# W002X.net
KiCad netlist of a schematic drawn in EAGLE
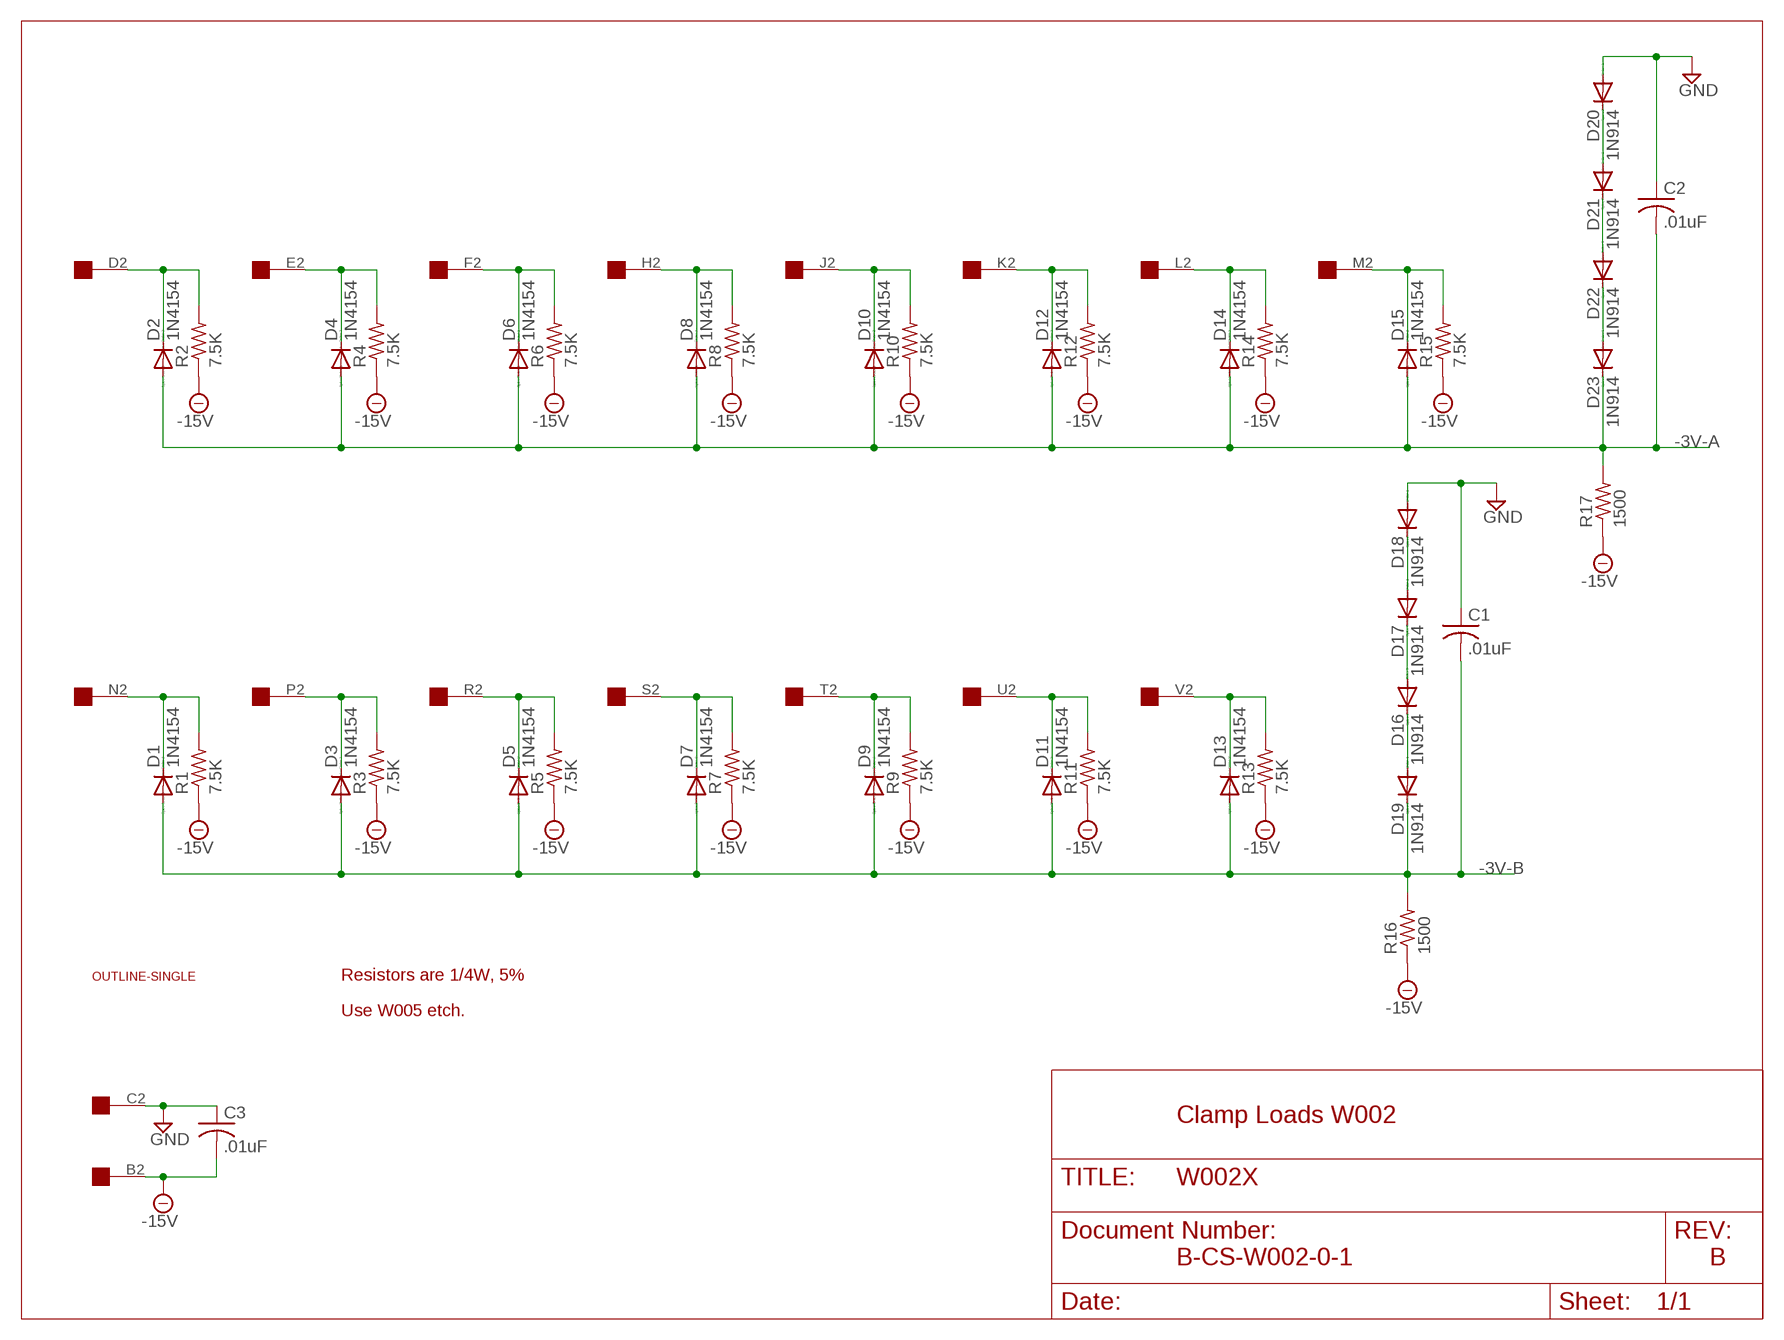
[diagram p0: schematic, sheet 1]

(export (version "E")
  (design (tool "Eeschema 10.0.6"))
  (components
    (comp (ref "C1")
      (value ".01uF")
      (footprint "eagle-import:C050-025X075")
      (libsource (lib "eagle-import") (part "C-US050-025X075"))
    )
    (comp (ref "C2")
      (value ".01uF")
      (footprint "eagle-import:C050-025X075")
      (libsource (lib "eagle-import") (part "C-US050-025X075"))
    )
    (comp (ref "C3")
      (value ".01uF")
      (footprint "eagle-import:C050-025X075")
      (libsource (lib "eagle-import") (part "C-US050-025X075"))
    )
    (comp (ref "D1")
      (value "1N4154")
      (footprint "eagle-import:DO35-10")
      (libsource (lib "eagle-import") (part "1N4148DO35-10"))
    )
    (comp (ref "D2")
      (value "1N4154")
      (footprint "eagle-import:DO35-10")
      (libsource (lib "eagle-import") (part "1N4148DO35-10"))
    )
    (comp (ref "D3")
      (value "1N4154")
      (footprint "eagle-import:DO35-10")
      (libsource (lib "eagle-import") (part "1N4148DO35-10"))
    )
    (comp (ref "D4")
      (value "1N4154")
      (footprint "eagle-import:DO35-10")
      (libsource (lib "eagle-import") (part "1N4148DO35-10"))
    )
    (comp (ref "D5")
      (value "1N4154")
      (footprint "eagle-import:DO35-10")
      (libsource (lib "eagle-import") (part "1N4148DO35-10"))
    )
    (comp (ref "D6")
      (value "1N4154")
      (footprint "eagle-import:DO35-10")
      (libsource (lib "eagle-import") (part "1N4148DO35-10"))
    )
    (comp (ref "D7")
      (value "1N4154")
      (footprint "eagle-import:DO35-10")
      (libsource (lib "eagle-import") (part "1N4148DO35-10"))
    )
    (comp (ref "D8")
      (value "1N4154")
      (footprint "eagle-import:DO35-10")
      (libsource (lib "eagle-import") (part "1N4148DO35-10"))
    )
    (comp (ref "D9")
      (value "1N4154")
      (footprint "eagle-import:DO35-10")
      (libsource (lib "eagle-import") (part "1N4148DO35-10"))
    )
    (comp (ref "D10")
      (value "1N4154")
      (footprint "eagle-import:DO35-10")
      (libsource (lib "eagle-import") (part "1N4148DO35-10"))
    )
    (comp (ref "D11")
      (value "1N4154")
      (footprint "eagle-import:DO35-10")
      (libsource (lib "eagle-import") (part "1N4148DO35-10"))
    )
    (comp (ref "D12")
      (value "1N4154")
      (footprint "eagle-import:DO35-10")
      (libsource (lib "eagle-import") (part "1N4148DO35-10"))
    )
    (comp (ref "D13")
      (value "1N4154")
      (footprint "eagle-import:DO35-10")
      (libsource (lib "eagle-import") (part "1N4148DO35-10"))
    )
    (comp (ref "D14")
      (value "1N4154")
      (footprint "eagle-import:DO35-10")
      (libsource (lib "eagle-import") (part "1N4148DO35-10"))
    )
    (comp (ref "D15")
      (value "1N4154")
      (footprint "eagle-import:DO35-10")
      (libsource (lib "eagle-import") (part "1N4148DO35-10"))
    )
    (comp (ref "D16")
      (value "1N914")
      (footprint "eagle-import:DO35-10")
      (libsource (lib "eagle-import") (part "1N4148DO35-10"))
    )
    (comp (ref "D17")
      (value "1N914")
      (footprint "eagle-import:DO35-10")
      (libsource (lib "eagle-import") (part "1N4148DO35-10"))
    )
    (comp (ref "D18")
      (value "1N914")
      (footprint "eagle-import:DO35-10")
      (libsource (lib "eagle-import") (part "1N4148DO35-10"))
    )
    (comp (ref "D19")
      (value "1N914")
      (footprint "eagle-import:DO35-10")
      (libsource (lib "eagle-import") (part "1N4148DO35-10"))
    )
    (comp (ref "D20")
      (value "1N914")
      (footprint "eagle-import:DO35-10")
      (libsource (lib "eagle-import") (part "1N4148DO35-10"))
    )
    (comp (ref "D21")
      (value "1N914")
      (footprint "eagle-import:DO35-10")
      (libsource (lib "eagle-import") (part "1N4148DO35-10"))
    )
    (comp (ref "D22")
      (value "1N914")
      (footprint "eagle-import:DO35-10")
      (libsource (lib "eagle-import") (part "1N4148DO35-10"))
    )
    (comp (ref "D23")
      (value "1N914")
      (footprint "eagle-import:DO35-10")
      (libsource (lib "eagle-import") (part "1N4148DO35-10"))
    )
    (comp (ref "R1")
      (value "7.5K")
      (footprint "eagle-import:0207_10")
      (libsource (lib "eagle-import") (part "R-US_0207/10"))
    )
    (comp (ref "R2")
      (value "7.5K")
      (footprint "eagle-import:0207_10")
      (libsource (lib "eagle-import") (part "R-US_0207/10"))
    )
    (comp (ref "R3")
      (value "7.5K")
      (footprint "eagle-import:0207_10")
      (libsource (lib "eagle-import") (part "R-US_0207/10"))
    )
    (comp (ref "R4")
      (value "7.5K")
      (footprint "eagle-import:0207_10")
      (libsource (lib "eagle-import") (part "R-US_0207/10"))
    )
    (comp (ref "R5")
      (value "7.5K")
      (footprint "eagle-import:0207_10")
      (libsource (lib "eagle-import") (part "R-US_0207/10"))
    )
    (comp (ref "R6")
      (value "7.5K")
      (footprint "eagle-import:0207_10")
      (libsource (lib "eagle-import") (part "R-US_0207/10"))
    )
    (comp (ref "R7")
      (value "7.5K")
      (footprint "eagle-import:0207_10")
      (libsource (lib "eagle-import") (part "R-US_0207/10"))
    )
    (comp (ref "R8")
      (value "7.5K")
      (footprint "eagle-import:0207_10")
      (libsource (lib "eagle-import") (part "R-US_0207/10"))
    )
    (comp (ref "R9")
      (value "7.5K")
      (footprint "eagle-import:0207_10")
      (libsource (lib "eagle-import") (part "R-US_0207/10"))
    )
    (comp (ref "R10")
      (value "7.5K")
      (footprint "eagle-import:0207_10")
      (libsource (lib "eagle-import") (part "R-US_0207/10"))
    )
    (comp (ref "R11")
      (value "7.5K")
      (footprint "eagle-import:0207_10")
      (libsource (lib "eagle-import") (part "R-US_0207/10"))
    )
    (comp (ref "R12")
      (value "7.5K")
      (footprint "eagle-import:0207_10")
      (libsource (lib "eagle-import") (part "R-US_0207/10"))
    )
    (comp (ref "R13")
      (value "7.5K")
      (footprint "eagle-import:0207_10")
      (libsource (lib "eagle-import") (part "R-US_0207/10"))
    )
    (comp (ref "R14")
      (value "7.5K")
      (footprint "eagle-import:0207_10")
      (libsource (lib "eagle-import") (part "R-US_0207/10"))
    )
    (comp (ref "R15")
      (value "7.5K")
      (footprint "eagle-import:0207_10")
      (libsource (lib "eagle-import") (part "R-US_0207/10"))
    )
    (comp (ref "R16")
      (value "1500")
      (footprint "eagle-import:0207_10")
      (libsource (lib "eagle-import") (part "R-US_0207/10"))
    )
    (comp (ref "R17")
      (value "1500")
      (footprint "eagle-import:0207_10")
      (libsource (lib "eagle-import") (part "R-US_0207/10"))
    )
    (comp (ref "U$1")
      (value "OUTLINE-SINGLE")
      (footprint "eagle-import:SINGLE")
      (libsource (lib "eagle-import") (part "OUTLINE-SINGLE"))
    )
    (comp (ref "U$2")
      (value "EDGE-1")
      (footprint "eagle-import:EDGE-CON1")
      (libsource (lib "eagle-import") (part "EDGE-1"))
    )
  )
  (nets
    (net (code "1") (name "-15V") (class "Default")
      (node (ref "C3") (pin "2") (pinfunction "2_2") (pintype "passive"))
      (node (ref "R1") (pin "1") (pinfunction "1_1") (pintype "passive"))
      (node (ref "R10") (pin "1") (pinfunction "1_1") (pintype "passive"))
      (node (ref "R11") (pin "1") (pinfunction "1_1") (pintype "passive"))
      (node (ref "R12") (pin "1") (pinfunction "1_1") (pintype "passive"))
      (node (ref "R13") (pin "1") (pinfunction "1_1") (pintype "passive"))
      (node (ref "R14") (pin "1") (pinfunction "1_1") (pintype "passive"))
      (node (ref "R15") (pin "1") (pinfunction "1_1") (pintype "passive"))
      (node (ref "R16") (pin "1") (pinfunction "1_1") (pintype "passive"))
      (node (ref "R17") (pin "1") (pinfunction "1_1") (pintype "passive"))
      (node (ref "R2") (pin "1") (pinfunction "1_1") (pintype "passive"))
      (node (ref "R3") (pin "1") (pinfunction "1_1") (pintype "passive"))
      (node (ref "R4") (pin "1") (pinfunction "1_1") (pintype "passive"))
      (node (ref "R5") (pin "1") (pinfunction "1_1") (pintype "passive"))
      (node (ref "R6") (pin "1") (pinfunction "1_1") (pintype "passive"))
      (node (ref "R7") (pin "1") (pinfunction "1_1") (pintype "passive"))
      (node (ref "R8") (pin "1") (pinfunction "1_1") (pintype "passive"))
      (node (ref "R9") (pin "1") (pinfunction "1_1") (pintype "passive"))
      (node (ref "U$2") (pin "B2") (pinfunction "1_B2") (pintype "bidirectional"))
    )
    (net (code "2") (name "/-3V-A") (class "Default")
      (node (ref "C2") (pin "2") (pinfunction "2_2") (pintype "passive"))
      (node (ref "D10") (pin "A") (pinfunction "A_A") (pintype "passive"))
      (node (ref "D12") (pin "A") (pinfunction "A_A") (pintype "passive"))
      (node (ref "D14") (pin "A") (pinfunction "A_A") (pintype "passive"))
      (node (ref "D15") (pin "A") (pinfunction "A_A") (pintype "passive"))
      (node (ref "D2") (pin "A") (pinfunction "A_A") (pintype "passive"))
      (node (ref "D23") (pin "C") (pinfunction "C_C") (pintype "passive"))
      (node (ref "D4") (pin "A") (pinfunction "A_A") (pintype "passive"))
      (node (ref "D6") (pin "A") (pinfunction "A_A") (pintype "passive"))
      (node (ref "D8") (pin "A") (pinfunction "A_A") (pintype "passive"))
      (node (ref "R17") (pin "2") (pinfunction "2_2") (pintype "passive"))
    )
    (net (code "3") (name "/-3V-B") (class "Default")
      (node (ref "C1") (pin "2") (pinfunction "2_2") (pintype "passive"))
      (node (ref "D1") (pin "A") (pinfunction "A_A") (pintype "passive"))
      (node (ref "D11") (pin "A") (pinfunction "A_A") (pintype "passive"))
      (node (ref "D13") (pin "A") (pinfunction "A_A") (pintype "passive"))
      (node (ref "D19") (pin "C") (pinfunction "C_C") (pintype "passive"))
      (node (ref "D3") (pin "A") (pinfunction "A_A") (pintype "passive"))
      (node (ref "D5") (pin "A") (pinfunction "A_A") (pintype "passive"))
      (node (ref "D7") (pin "A") (pinfunction "A_A") (pintype "passive"))
      (node (ref "D9") (pin "A") (pinfunction "A_A") (pintype "passive"))
      (node (ref "R16") (pin "2") (pinfunction "2_2") (pintype "passive"))
    )
    (net (code "4") (name "GND") (class "Default")
      (node (ref "C1") (pin "1") (pinfunction "1_1") (pintype "passive"))
      (node (ref "C2") (pin "1") (pinfunction "1_1") (pintype "passive"))
      (node (ref "C3") (pin "1") (pinfunction "1_1") (pintype "passive"))
      (node (ref "D18") (pin "A") (pinfunction "A_A") (pintype "passive"))
      (node (ref "D20") (pin "A") (pinfunction "A_A") (pintype "passive"))
      (node (ref "U$2") (pin "C2") (pinfunction "1_C2") (pintype "bidirectional"))
    )
    (net (code "5") (name "Net-(D16-PadA)") (class "Default")
      (node (ref "D16") (pin "A") (pinfunction "A_A") (pintype "passive"))
      (node (ref "D17") (pin "C") (pinfunction "C_C") (pintype "passive"))
    )
    (net (code "6") (name "Net-(D16-PadC)") (class "Default")
      (node (ref "D16") (pin "C") (pinfunction "C_C") (pintype "passive"))
      (node (ref "D19") (pin "A") (pinfunction "A_A") (pintype "passive"))
    )
    (net (code "7") (name "Net-(D17-PadA)") (class "Default")
      (node (ref "D17") (pin "A") (pinfunction "A_A") (pintype "passive"))
      (node (ref "D18") (pin "C") (pinfunction "C_C") (pintype "passive"))
    )
    (net (code "8") (name "Net-(D20-PadC)") (class "Default")
      (node (ref "D20") (pin "C") (pinfunction "C_C") (pintype "passive"))
      (node (ref "D21") (pin "A") (pinfunction "A_A") (pintype "passive"))
    )
    (net (code "9") (name "Net-(D21-PadC)") (class "Default")
      (node (ref "D21") (pin "C") (pinfunction "C_C") (pintype "passive"))
      (node (ref "D22") (pin "A") (pinfunction "A_A") (pintype "passive"))
    )
    (net (code "10") (name "Net-(D22-PadC)") (class "Default")
      (node (ref "D22") (pin "C") (pinfunction "C_C") (pintype "passive"))
      (node (ref "D23") (pin "A") (pinfunction "A_A") (pintype "passive"))
    )
    (net (code "11") (name "Net-(U$2D-1)") (class "Default")
      (node (ref "D2") (pin "C") (pinfunction "C_C") (pintype "passive"))
      (node (ref "R2") (pin "2") (pinfunction "2_2") (pintype "passive"))
      (node (ref "U$2") (pin "D2") (pinfunction "1_D2") (pintype "bidirectional"))
    )
    (net (code "12") (name "Net-(U$2E-1)") (class "Default")
      (node (ref "D4") (pin "C") (pinfunction "C_C") (pintype "passive"))
      (node (ref "R4") (pin "2") (pinfunction "2_2") (pintype "passive"))
      (node (ref "U$2") (pin "E2") (pinfunction "1_E2") (pintype "bidirectional"))
    )
    (net (code "13") (name "Net-(U$2F-1)") (class "Default")
      (node (ref "D6") (pin "C") (pinfunction "C_C") (pintype "passive"))
      (node (ref "R6") (pin "2") (pinfunction "2_2") (pintype "passive"))
      (node (ref "U$2") (pin "F2") (pinfunction "1_F2") (pintype "bidirectional"))
    )
    (net (code "14") (name "Net-(U$2G-1)") (class "Default")
      (node (ref "D8") (pin "C") (pinfunction "C_C") (pintype "passive"))
      (node (ref "R8") (pin "2") (pinfunction "2_2") (pintype "passive"))
      (node (ref "U$2") (pin "H2") (pinfunction "1_H2") (pintype "bidirectional"))
    )
    (net (code "15") (name "Net-(U$2H-1)") (class "Default")
      (node (ref "D10") (pin "C") (pinfunction "C_C") (pintype "passive"))
      (node (ref "R10") (pin "2") (pinfunction "2_2") (pintype "passive"))
      (node (ref "U$2") (pin "J2") (pinfunction "1_J2") (pintype "bidirectional"))
    )
    (net (code "16") (name "Net-(U$2I-1)") (class "Default")
      (node (ref "D12") (pin "C") (pinfunction "C_C") (pintype "passive"))
      (node (ref "R12") (pin "2") (pinfunction "2_2") (pintype "passive"))
      (node (ref "U$2") (pin "K2") (pinfunction "1_K2") (pintype "bidirectional"))
    )
    (net (code "17") (name "Net-(U$2J-1)") (class "Default")
      (node (ref "D14") (pin "C") (pinfunction "C_C") (pintype "passive"))
      (node (ref "R14") (pin "2") (pinfunction "2_2") (pintype "passive"))
      (node (ref "U$2") (pin "L2") (pinfunction "1_L2") (pintype "bidirectional"))
    )
    (net (code "18") (name "Net-(U$2K-1)") (class "Default")
      (node (ref "D15") (pin "C") (pinfunction "C_C") (pintype "passive"))
      (node (ref "R15") (pin "2") (pinfunction "2_2") (pintype "passive"))
      (node (ref "U$2") (pin "M2") (pinfunction "1_M2") (pintype "bidirectional"))
    )
    (net (code "19") (name "Net-(U$2L-1)") (class "Default")
      (node (ref "D1") (pin "C") (pinfunction "C_C") (pintype "passive"))
      (node (ref "R1") (pin "2") (pinfunction "2_2") (pintype "passive"))
      (node (ref "U$2") (pin "N2") (pinfunction "1_N2") (pintype "bidirectional"))
    )
    (net (code "20") (name "Net-(U$2M-1)") (class "Default")
      (node (ref "D3") (pin "C") (pinfunction "C_C") (pintype "passive"))
      (node (ref "R3") (pin "2") (pinfunction "2_2") (pintype "passive"))
      (node (ref "U$2") (pin "P2") (pinfunction "1_P2") (pintype "bidirectional"))
    )
    (net (code "21") (name "Net-(U$2N-1)") (class "Default")
      (node (ref "D5") (pin "C") (pinfunction "C_C") (pintype "passive"))
      (node (ref "R5") (pin "2") (pinfunction "2_2") (pintype "passive"))
      (node (ref "U$2") (pin "R2") (pinfunction "1_R2") (pintype "bidirectional"))
    )
    (net (code "22") (name "Net-(U$2O-1)") (class "Default")
      (node (ref "D7") (pin "C") (pinfunction "C_C") (pintype "passive"))
      (node (ref "R7") (pin "2") (pinfunction "2_2") (pintype "passive"))
      (node (ref "U$2") (pin "S2") (pinfunction "1_S2") (pintype "bidirectional"))
    )
    (net (code "23") (name "Net-(U$2P-1)") (class "Default")
      (node (ref "D9") (pin "C") (pinfunction "C_C") (pintype "passive"))
      (node (ref "R9") (pin "2") (pinfunction "2_2") (pintype "passive"))
      (node (ref "U$2") (pin "T2") (pinfunction "1_T2") (pintype "bidirectional"))
    )
    (net (code "24") (name "Net-(U$2Q-1)") (class "Default")
      (node (ref "D11") (pin "C") (pinfunction "C_C") (pintype "passive"))
      (node (ref "R11") (pin "2") (pinfunction "2_2") (pintype "passive"))
      (node (ref "U$2") (pin "U2") (pinfunction "1_U2") (pintype "bidirectional"))
    )
    (net (code "25") (name "Net-(U$2R-1)") (class "Default")
      (node (ref "D13") (pin "C") (pinfunction "C_C") (pintype "passive"))
      (node (ref "R13") (pin "2") (pinfunction "2_2") (pintype "passive"))
      (node (ref "U$2") (pin "V2") (pinfunction "1_V2") (pintype "bidirectional"))
    )
  )
)
